# Mounting_PCB_B.net
KiCad netlist of a schematic drawn in Altium Designer
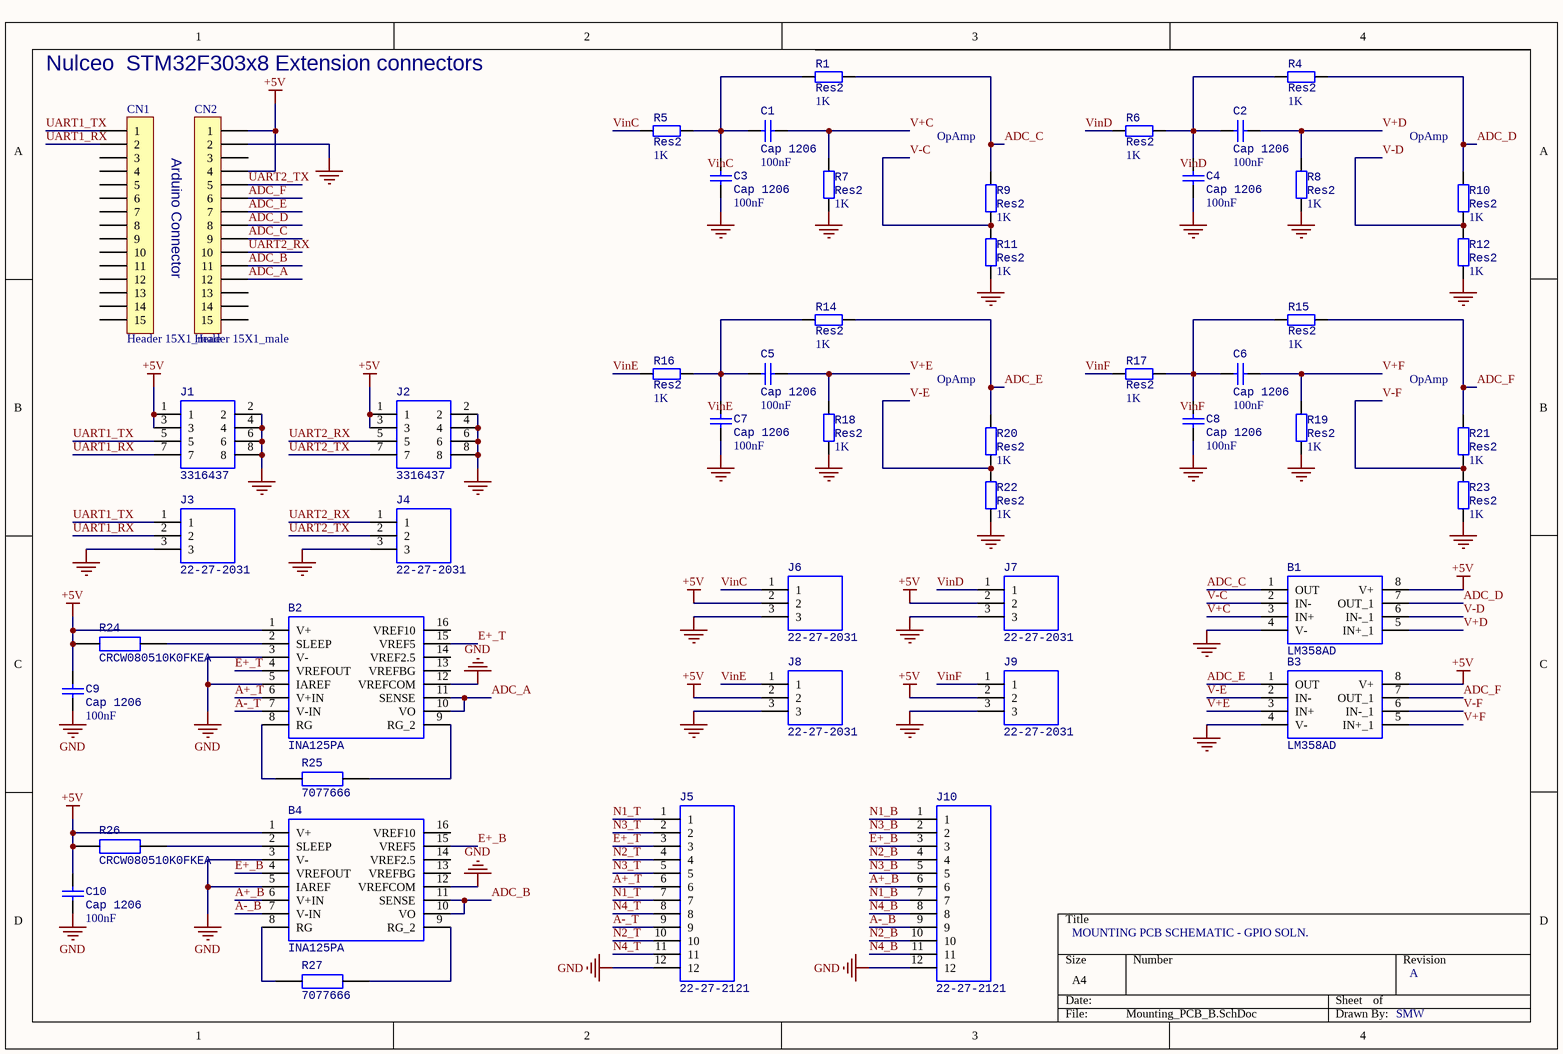
[diagram p0: Mounting_PCB_B.SchDoc]

(export (version "E")
  (design (tool "Eeschema 10.0.6"))
  (components
    (comp (ref "B1")
      (value "LM358AD")
      (footprint "SOIC127P600X175-8N")
      (description "LM358AD, Dual Operational Amplifier 1.1MHz 5 to 28V, 8-Pin SO")
      (fields (field (name "RS PART NUMBER") "1657542"))
      (libsource (lib "LM358AD") (part "LM358AD"))
    )
    (comp (ref "B2")
      (value "INA125PA")
      (footprint "DIP254P762X508-16")
      (description "Instrumentation Amplifier with Precision Voltage Reference")
      (fields (field (name "RS PART NUMBER") "2521593P"))
      (libsource (lib "INA125PA") (part "INA125PA"))
    )
    (comp (ref "B3")
      (value "LM358AD")
      (footprint "SOIC127P600X175-8N")
      (description "LM358AD, Dual Operational Amplifier 1.1MHz 5 to 28V, 8-Pin SO")
      (fields (field (name "RS PART NUMBER") "1657542"))
      (libsource (lib "LM358AD") (part "LM358AD"))
    )
    (comp (ref "B4")
      (value "INA125PA")
      (footprint "DIP254P762X508-16")
      (description "Instrumentation Amplifier with Precision Voltage Reference")
      (fields (field (name "RS PART NUMBER") "2521593P"))
      (libsource (lib "INA125PA") (part "INA125PA"))
    )
    (comp (ref "C1")
      (value "Cap 1206")
      (footprint "C1206")
      (description "Capacitor (Semiconductor SIM Model)")
      (fields (field (name "ALTIUM_VALUE") "100nF") (field (name "PUBLISHER") "Altium Limited"))
      (libsource (lib "Miscellaneous Devices") (part "Cap Semi"))
    )
    (comp (ref "C2")
      (value "Cap 1206")
      (footprint "C1206")
      (description "Capacitor (Semiconductor SIM Model)")
      (fields (field (name "ALTIUM_VALUE") "100nF") (field (name "PUBLISHER") "Altium Limited"))
      (libsource (lib "Miscellaneous Devices") (part "Cap Semi"))
    )
    (comp (ref "C3")
      (value "Cap 1206")
      (footprint "C1206")
      (description "Capacitor (Semiconductor SIM Model)")
      (fields (field (name "ALTIUM_VALUE") "100nF") (field (name "PUBLISHER") "Altium Limited"))
      (libsource (lib "Miscellaneous Devices") (part "Cap Semi"))
    )
    (comp (ref "C4")
      (value "Cap 1206")
      (footprint "C1206")
      (description "Capacitor (Semiconductor SIM Model)")
      (fields (field (name "ALTIUM_VALUE") "100nF") (field (name "PUBLISHER") "Altium Limited"))
      (libsource (lib "Miscellaneous Devices") (part "Cap Semi"))
    )
    (comp (ref "C5")
      (value "Cap 1206")
      (footprint "C1206")
      (description "Capacitor (Semiconductor SIM Model)")
      (fields (field (name "ALTIUM_VALUE") "100nF") (field (name "PUBLISHER") "Altium Limited"))
      (libsource (lib "Miscellaneous Devices") (part "Cap Semi"))
    )
    (comp (ref "C6")
      (value "Cap 1206")
      (footprint "C1206")
      (description "Capacitor (Semiconductor SIM Model)")
      (fields (field (name "ALTIUM_VALUE") "100nF") (field (name "PUBLISHER") "Altium Limited"))
      (libsource (lib "Miscellaneous Devices") (part "Cap Semi"))
    )
    (comp (ref "C7")
      (value "Cap 1206")
      (footprint "C1206")
      (description "Capacitor (Semiconductor SIM Model)")
      (fields (field (name "ALTIUM_VALUE") "100nF") (field (name "PUBLISHER") "Altium Limited"))
      (libsource (lib "Miscellaneous Devices") (part "Cap Semi"))
    )
    (comp (ref "C8")
      (value "Cap 1206")
      (footprint "C1206")
      (description "Capacitor (Semiconductor SIM Model)")
      (fields (field (name "ALTIUM_VALUE") "100nF") (field (name "PUBLISHER") "Altium Limited"))
      (libsource (lib "Miscellaneous Devices") (part "Cap Semi"))
    )
    (comp (ref "C9")
      (value "Cap 1206")
      (footprint "C1206")
      (description "Capacitor (Semiconductor SIM Model)")
      (fields (field (name "ALTIUM_VALUE") "100nF") (field (name "PUBLISHER") "Altium Limited"))
      (libsource (lib "Miscellaneous Devices") (part "Cap Semi"))
    )
    (comp (ref "C10")
      (value "Cap 1206")
      (footprint "C1206")
      (description "Capacitor (Semiconductor SIM Model)")
      (fields (field (name "ALTIUM_VALUE") "100nF") (field (name "PUBLISHER") "Altium Limited"))
      (libsource (lib "Miscellaneous Devices") (part "Cap Semi"))
    )
    (comp (ref "CN1")
      (value "Header 15X1_male")
      (footprint "HDR_1x15_2R54_V_F")
      (description "Header, 10-Pin, Single row,female")
      (fields (field (name "PUBLISHER") "Altium Limited"))
      (libsource (lib "") (part "Header 15X1_Female_1_1"))
    )
    (comp (ref "CN2")
      (value "Header 15X1_male")
      (footprint "HDR_1x15_2R54_V_F")
      (description "Header, 10-Pin, Single row,female")
      (fields (field (name "PUBLISHER") "Altium Limited"))
      (libsource (lib "MB1180") (part "Header 15X1_Female_1"))
    )
    (comp (ref "J1") (value "3316437") (footprint "RJ45-8") (libsource (lib "3316437") (part "3316437")))
    (comp (ref "J2") (value "3316437") (footprint "RJ45-8") (libsource (lib "3316437") (part "3316437")))
    (comp (ref "J3")
      (value "22-27-2031")
      (footprint "SHDR3W64P0X254_1X3_762X580X1170P")
      (fields (field (name "RS PART NUMBER") "1707102"))
      (libsource (lib "22-27-2031") (part "22-27-2031"))
    )
    (comp (ref "J4")
      (value "22-27-2031")
      (footprint "SHDR3W64P0X254_1X3_762X580X1170P")
      (fields (field (name "RS PART NUMBER") "1707102"))
      (libsource (lib "22-27-2031") (part "22-27-2031"))
    )
    (comp (ref "J5")
      (value "22-27-2121")
      (footprint "HDRV12W64P0X254_1X12_3048X580X1170P")
      (fields (field (name "RS PART NUMBER") "1707108"))
      (libsource (lib "22-27-2121") (part "22-27-2121"))
    )
    (comp (ref "J6")
      (value "22-27-2031")
      (footprint "SHDR3W64P0X254_1X3_762X580X1170P")
      (fields (field (name "RS PART NUMBER") "1707102"))
      (libsource (lib "22-27-2031") (part "22-27-2031"))
    )
    (comp (ref "J7")
      (value "22-27-2031")
      (footprint "SHDR3W64P0X254_1X3_762X580X1170P")
      (fields (field (name "RS PART NUMBER") "1707102"))
      (libsource (lib "22-27-2031") (part "22-27-2031"))
    )
    (comp (ref "J8")
      (value "22-27-2031")
      (footprint "SHDR3W64P0X254_1X3_762X580X1170P")
      (fields (field (name "RS PART NUMBER") "1707102"))
      (libsource (lib "22-27-2031") (part "22-27-2031"))
    )
    (comp (ref "J9")
      (value "22-27-2031")
      (footprint "SHDR3W64P0X254_1X3_762X580X1170P")
      (fields (field (name "RS PART NUMBER") "1707102"))
      (libsource (lib "22-27-2031") (part "22-27-2031"))
    )
    (comp (ref "J10")
      (value "22-27-2121")
      (footprint "HDRV12W64P0X254_1X12_3048X580X1170P")
      (fields (field (name "RS PART NUMBER") "1707108"))
      (libsource (lib "22-27-2121") (part "22-27-2121"))
    )
    (comp (ref "R1")
      (value "Res2")
      (footprint "C1206")
      (description "Resistor")
      (fields (field (name "ALTIUM_VALUE") "1K") (field (name "PUBLISHER") "Altium Limited"))
      (libsource (lib "") (part "Res2_1"))
    )
    (comp (ref "R4")
      (value "Res2")
      (footprint "C1206")
      (description "Resistor")
      (fields (field (name "ALTIUM_VALUE") "1K") (field (name "PUBLISHER") "Altium Limited"))
      (libsource (lib "") (part "Res2_1"))
    )
    (comp (ref "R5")
      (value "Res2")
      (footprint "C1206")
      (description "Resistor")
      (fields (field (name "ALTIUM_VALUE") "1K") (field (name "PUBLISHER") "Altium Limited"))
      (libsource (lib "") (part "Res2_1"))
    )
    (comp (ref "R6")
      (value "Res2")
      (footprint "C1206")
      (description "Resistor")
      (fields (field (name "ALTIUM_VALUE") "1K") (field (name "PUBLISHER") "Altium Limited"))
      (libsource (lib "") (part "Res2_1"))
    )
    (comp (ref "R7")
      (value "Res2")
      (footprint "C1206")
      (description "Resistor")
      (fields (field (name "ALTIUM_VALUE") "1K") (field (name "PUBLISHER") "Altium Limited"))
      (libsource (lib "Miscellaneous Devices") (part "Res2"))
    )
    (comp (ref "R8")
      (value "Res2")
      (footprint "C1206")
      (description "Resistor")
      (fields (field (name "ALTIUM_VALUE") "1K") (field (name "PUBLISHER") "Altium Limited"))
      (libsource (lib "Miscellaneous Devices") (part "Res2"))
    )
    (comp (ref "R9")
      (value "Res2")
      (footprint "C1206")
      (description "Resistor")
      (fields (field (name "ALTIUM_VALUE") "1K") (field (name "PUBLISHER") "Altium Limited"))
      (libsource (lib "Miscellaneous Devices") (part "Res2"))
    )
    (comp (ref "R10")
      (value "Res2")
      (footprint "C1206")
      (description "Resistor")
      (fields (field (name "ALTIUM_VALUE") "1K") (field (name "PUBLISHER") "Altium Limited"))
      (libsource (lib "Miscellaneous Devices") (part "Res2"))
    )
    (comp (ref "R11")
      (value "Res2")
      (footprint "C1206")
      (description "Resistor")
      (fields (field (name "ALTIUM_VALUE") "1K") (field (name "PUBLISHER") "Altium Limited"))
      (libsource (lib "Miscellaneous Devices") (part "Res2"))
    )
    (comp (ref "R12")
      (value "Res2")
      (footprint "C1206")
      (description "Resistor")
      (fields (field (name "ALTIUM_VALUE") "1K") (field (name "PUBLISHER") "Altium Limited"))
      (libsource (lib "Miscellaneous Devices") (part "Res2"))
    )
    (comp (ref "R14")
      (value "Res2")
      (footprint "C1206")
      (description "Resistor")
      (fields (field (name "ALTIUM_VALUE") "1K") (field (name "PUBLISHER") "Altium Limited"))
      (libsource (lib "") (part "Res2_1"))
    )
    (comp (ref "R15")
      (value "Res2")
      (footprint "C1206")
      (description "Resistor")
      (fields (field (name "ALTIUM_VALUE") "1K") (field (name "PUBLISHER") "Altium Limited"))
      (libsource (lib "") (part "Res2_1"))
    )
    (comp (ref "R16")
      (value "Res2")
      (footprint "C1206")
      (description "Resistor")
      (fields (field (name "ALTIUM_VALUE") "1K") (field (name "PUBLISHER") "Altium Limited"))
      (libsource (lib "") (part "Res2_1"))
    )
    (comp (ref "R17")
      (value "Res2")
      (footprint "C1206")
      (description "Resistor")
      (fields (field (name "ALTIUM_VALUE") "1K") (field (name "PUBLISHER") "Altium Limited"))
      (libsource (lib "") (part "Res2_1"))
    )
    (comp (ref "R18")
      (value "Res2")
      (footprint "C1206")
      (description "Resistor")
      (fields (field (name "ALTIUM_VALUE") "1K") (field (name "PUBLISHER") "Altium Limited"))
      (libsource (lib "Miscellaneous Devices") (part "Res2"))
    )
    (comp (ref "R19")
      (value "Res2")
      (footprint "C1206")
      (description "Resistor")
      (fields (field (name "ALTIUM_VALUE") "1K") (field (name "PUBLISHER") "Altium Limited"))
      (libsource (lib "Miscellaneous Devices") (part "Res2"))
    )
    (comp (ref "R20")
      (value "Res2")
      (footprint "C1206")
      (description "Resistor")
      (fields (field (name "ALTIUM_VALUE") "1K") (field (name "PUBLISHER") "Altium Limited"))
      (libsource (lib "Miscellaneous Devices") (part "Res2"))
    )
    (comp (ref "R21")
      (value "Res2")
      (footprint "C1206")
      (description "Resistor")
      (fields (field (name "ALTIUM_VALUE") "1K") (field (name "PUBLISHER") "Altium Limited"))
      (libsource (lib "Miscellaneous Devices") (part "Res2"))
    )
    (comp (ref "R22")
      (value "Res2")
      (footprint "C1206")
      (description "Resistor")
      (fields (field (name "ALTIUM_VALUE") "1K") (field (name "PUBLISHER") "Altium Limited"))
      (libsource (lib "Miscellaneous Devices") (part "Res2"))
    )
    (comp (ref "R23")
      (value "Res2")
      (footprint "C1206")
      (description "Resistor")
      (fields (field (name "ALTIUM_VALUE") "1K") (field (name "PUBLISHER") "Altium Limited"))
      (libsource (lib "Miscellaneous Devices") (part "Res2"))
    )
    (comp (ref "R24")
      (value "CRCW080510K0FKEA")
      (footprint "RESC2012X50N")
      (fields (field (name "RS PART NUMBER") "1694499"))
      (libsource (lib "CRCW080510K0FKEA") (part "CRCW080510K0FKEA"))
    )
    (comp (ref "R25")
      (value "7077666")
      (footprint "RESAD1550W58L630D230")
      (description "RS Pro RS Series Axial Carbon Resistor 1k 5% 0.25W -500  +350ppm/C")
      (libsource (lib "7077666") (part "7077666"))
    )
    (comp (ref "R26")
      (value "CRCW080510K0FKEA")
      (footprint "RESC2012X50N")
      (fields (field (name "RS PART NUMBER") "1694499"))
      (libsource (lib "CRCW080510K0FKEA") (part "CRCW080510K0FKEA"))
    )
    (comp (ref "R27")
      (value "7077666")
      (footprint "RESAD1550W58L630D230")
      (description "RS Pro RS Series Axial Carbon Resistor 1k 5% 0.25W -500  +350ppm/C")
      (libsource (lib "7077666") (part "7077666"))
    )
  )
  (nets
    (net (code "1") (name "+5V") (class "Default")
      (node (ref "B1") (pin "8") (pinfunction "V+_8") (pintype "passive"))
      (node (ref "B2") (pin "1") (pinfunction "V+_1") (pintype "passive"))
      (node (ref "B3") (pin "8") (pinfunction "V+_8") (pintype "passive"))
      (node (ref "B4") (pin "1") (pinfunction "V+_1") (pintype "passive"))
      (node (ref "C10") (pin "2") (pinfunction "2_2") (pintype "passive"))
      (node (ref "C9") (pin "2") (pinfunction "2_2") (pintype "passive"))
      (node (ref "CN2") (pin "1") (pinfunction "1_1") (pintype "passive"))
      (node (ref "CN2") (pin "4") (pinfunction "4_4") (pintype "passive"))
      (node (ref "J1") (pin "1") (pinfunction "1_1") (pintype "passive"))
      (node (ref "J1") (pin "3") (pinfunction "3_3") (pintype "passive"))
      (node (ref "J2") (pin "1") (pinfunction "1_1") (pintype "passive"))
      (node (ref "J2") (pin "3") (pinfunction "3_3") (pintype "passive"))
      (node (ref "J6") (pin "2") (pinfunction "2_2") (pintype "passive"))
      (node (ref "J7") (pin "2") (pinfunction "2_2") (pintype "passive"))
      (node (ref "J8") (pin "2") (pinfunction "2_2") (pintype "passive"))
      (node (ref "J9") (pin "2") (pinfunction "2_2") (pintype "passive"))
      (node (ref "R24") (pin "1") (pinfunction "1_1") (pintype "passive"))
      (node (ref "R26") (pin "1") (pinfunction "1_1") (pintype "passive"))
    )
    (net (code "2") (name "/A+_B") (class "Default")
      (node (ref "B4") (pin "6") (pinfunction "V+IN_6") (pintype "passive"))
      (node (ref "J10") (pin "6") (pinfunction "6_6") (pintype "passive"))
    )
    (net (code "3") (name "/A+_T") (class "Default")
      (node (ref "B2") (pin "6") (pinfunction "V+IN_6") (pintype "passive"))
      (node (ref "J5") (pin "6") (pinfunction "6_6") (pintype "passive"))
    )
    (net (code "4") (name "/A-_B") (class "Default")
      (node (ref "B4") (pin "7") (pinfunction "V-IN_7") (pintype "passive"))
      (node (ref "J10") (pin "9") (pinfunction "9_9") (pintype "passive"))
    )
    (net (code "5") (name "/A-_T") (class "Default")
      (node (ref "B2") (pin "7") (pinfunction "V-IN_7") (pintype "passive"))
      (node (ref "J5") (pin "9") (pinfunction "9_9") (pintype "passive"))
    )
    (net (code "6") (name "/ADC_A") (class "Default")
      (node (ref "B2") (pin "10") (pinfunction "VO_10") (pintype "passive"))
      (node (ref "B2") (pin "11") (pinfunction "SENSE_11") (pintype "passive"))
      (node (ref "CN2") (pin "12") (pinfunction "12_12") (pintype "passive"))
    )
    (net (code "7") (name "/ADC_B") (class "Default")
      (node (ref "B4") (pin "10") (pinfunction "VO_10") (pintype "passive"))
      (node (ref "B4") (pin "11") (pinfunction "SENSE_11") (pintype "passive"))
      (node (ref "CN2") (pin "11") (pinfunction "11_11") (pintype "passive"))
    )
    (net (code "8") (name "/ADC_C") (class "Default")
      (node (ref "B1") (pin "1") (pinfunction "OUT_1") (pintype "passive"))
      (node (ref "CN2") (pin "9") (pinfunction "9_9") (pintype "passive"))
      (node (ref "R1") (pin "2") (pinfunction "2_2") (pintype "passive"))
      (node (ref "R9") (pin "2") (pinfunction "2_2") (pintype "passive"))
    )
    (net (code "9") (name "/ADC_D") (class "Default")
      (node (ref "B1") (pin "7") (pinfunction "OUT_1_7") (pintype "passive"))
      (node (ref "CN2") (pin "8") (pinfunction "8_8") (pintype "passive"))
      (node (ref "R10") (pin "2") (pinfunction "2_2") (pintype "passive"))
      (node (ref "R4") (pin "2") (pinfunction "2_2") (pintype "passive"))
    )
    (net (code "10") (name "/ADC_E") (class "Default")
      (node (ref "B3") (pin "1") (pinfunction "OUT_1") (pintype "passive"))
      (node (ref "CN2") (pin "7") (pinfunction "7_7") (pintype "passive"))
      (node (ref "R14") (pin "2") (pinfunction "2_2") (pintype "passive"))
      (node (ref "R20") (pin "2") (pinfunction "2_2") (pintype "passive"))
    )
    (net (code "11") (name "/ADC_F") (class "Default")
      (node (ref "B3") (pin "7") (pinfunction "OUT_1_7") (pintype "passive"))
      (node (ref "CN2") (pin "6") (pinfunction "6_6") (pintype "passive"))
      (node (ref "R15") (pin "2") (pinfunction "2_2") (pintype "passive"))
      (node (ref "R21") (pin "2") (pinfunction "2_2") (pintype "passive"))
    )
    (net (code "12") (name "/E+_B") (class "Default")
      (node (ref "B4") (pin "15") (pinfunction "VREF5_15") (pintype "passive"))
      (node (ref "B4") (pin "4") (pinfunction "VREFOUT_4") (pintype "passive"))
      (node (ref "J10") (pin "3") (pinfunction "3_3") (pintype "passive"))
    )
    (net (code "13") (name "/E+_T") (class "Default")
      (node (ref "B2") (pin "15") (pinfunction "VREF5_15") (pintype "passive"))
      (node (ref "B2") (pin "4") (pinfunction "VREFOUT_4") (pintype "passive"))
      (node (ref "J5") (pin "3") (pinfunction "3_3") (pintype "passive"))
    )
    (net (code "14") (name "/N1_B") (class "Default")
      (node (ref "J10") (pin "1") (pinfunction "1_1") (pintype "passive"))
      (node (ref "J10") (pin "7") (pinfunction "7_7") (pintype "passive"))
    )
    (net (code "15") (name "/N1_T") (class "Default")
      (node (ref "J5") (pin "1") (pinfunction "1_1") (pintype "passive"))
      (node (ref "J5") (pin "7") (pinfunction "7_7") (pintype "passive"))
    )
    (net (code "16") (name "/N2_B") (class "Default")
      (node (ref "J10") (pin "10") (pinfunction "10_10") (pintype "passive"))
      (node (ref "J10") (pin "4") (pinfunction "4_4") (pintype "passive"))
    )
    (net (code "17") (name "/N2_T") (class "Default")
      (node (ref "J5") (pin "10") (pinfunction "10_10") (pintype "passive"))
      (node (ref "J5") (pin "4") (pinfunction "4_4") (pintype "passive"))
    )
    (net (code "18") (name "/N3_B") (class "Default")
      (node (ref "J10") (pin "2") (pinfunction "2_2") (pintype "passive"))
      (node (ref "J10") (pin "5") (pinfunction "5_5") (pintype "passive"))
    )
    (net (code "19") (name "/N3_T") (class "Default")
      (node (ref "J5") (pin "2") (pinfunction "2_2") (pintype "passive"))
      (node (ref "J5") (pin "5") (pinfunction "5_5") (pintype "passive"))
    )
    (net (code "20") (name "/N4_B") (class "Default")
      (node (ref "J10") (pin "11") (pinfunction "11_11") (pintype "passive"))
      (node (ref "J10") (pin "8") (pinfunction "8_8") (pintype "passive"))
    )
    (net (code "21") (name "/N4_T") (class "Default")
      (node (ref "J5") (pin "11") (pinfunction "11_11") (pintype "passive"))
      (node (ref "J5") (pin "8") (pinfunction "8_8") (pintype "passive"))
    )
    (net (code "22") (name "/UART1_RX") (class "Default")
      (node (ref "CN1") (pin "2") (pinfunction "2_2") (pintype "passive"))
      (node (ref "J1") (pin "7") (pinfunction "7_7") (pintype "passive"))
      (node (ref "J3") (pin "2") (pinfunction "2_2") (pintype "passive"))
    )
    (net (code "23") (name "/UART1_TX") (class "Default")
      (node (ref "CN1") (pin "1") (pinfunction "1_1") (pintype "passive"))
      (node (ref "J1") (pin "5") (pinfunction "5_5") (pintype "passive"))
      (node (ref "J3") (pin "1") (pinfunction "1_1") (pintype "passive"))
    )
    (net (code "24") (name "/UART2_RX") (class "Default")
      (node (ref "CN2") (pin "10") (pinfunction "10_10") (pintype "passive"))
      (node (ref "J2") (pin "5") (pinfunction "5_5") (pintype "passive"))
      (node (ref "J4") (pin "1") (pinfunction "1_1") (pintype "passive"))
    )
    (net (code "25") (name "/UART2_TX") (class "Default")
      (node (ref "CN2") (pin "5") (pinfunction "5_5") (pintype "passive"))
      (node (ref "J2") (pin "7") (pinfunction "7_7") (pintype "passive"))
      (node (ref "J4") (pin "2") (pinfunction "2_2") (pintype "passive"))
    )
    (net (code "26") (name "/V+C") (class "Default")
      (node (ref "B1") (pin "3") (pinfunction "IN+_3") (pintype "passive"))
      (node (ref "C1") (pin "1") (pinfunction "1_1") (pintype "passive"))
      (node (ref "R7") (pin "2") (pinfunction "2_2") (pintype "passive"))
    )
    (net (code "27") (name "/V+D") (class "Default")
      (node (ref "B1") (pin "5") (pinfunction "IN+_1_5") (pintype "passive"))
      (node (ref "C2") (pin "1") (pinfunction "1_1") (pintype "passive"))
      (node (ref "R8") (pin "2") (pinfunction "2_2") (pintype "passive"))
    )
    (net (code "28") (name "/V+E") (class "Default")
      (node (ref "B3") (pin "3") (pinfunction "IN+_3") (pintype "passive"))
      (node (ref "C5") (pin "1") (pinfunction "1_1") (pintype "passive"))
      (node (ref "R18") (pin "2") (pinfunction "2_2") (pintype "passive"))
    )
    (net (code "29") (name "/V+F") (class "Default")
      (node (ref "B3") (pin "5") (pinfunction "IN+_1_5") (pintype "passive"))
      (node (ref "C6") (pin "1") (pinfunction "1_1") (pintype "passive"))
      (node (ref "R19") (pin "2") (pinfunction "2_2") (pintype "passive"))
    )
    (net (code "30") (name "/V-C") (class "Default")
      (node (ref "B1") (pin "2") (pinfunction "IN-_2") (pintype "passive"))
      (node (ref "R11") (pin "2") (pinfunction "2_2") (pintype "passive"))
      (node (ref "R9") (pin "1") (pinfunction "1_1") (pintype "passive"))
    )
    (net (code "31") (name "/V-D") (class "Default")
      (node (ref "B1") (pin "6") (pinfunction "IN-_1_6") (pintype "passive"))
      (node (ref "R10") (pin "1") (pinfunction "1_1") (pintype "passive"))
      (node (ref "R12") (pin "2") (pinfunction "2_2") (pintype "passive"))
    )
    (net (code "32") (name "/V-E") (class "Default")
      (node (ref "B3") (pin "2") (pinfunction "IN-_2") (pintype "passive"))
      (node (ref "R20") (pin "1") (pinfunction "1_1") (pintype "passive"))
      (node (ref "R22") (pin "2") (pinfunction "2_2") (pintype "passive"))
    )
    (net (code "33") (name "/V-F") (class "Default")
      (node (ref "B3") (pin "6") (pinfunction "IN-_1_6") (pintype "passive"))
      (node (ref "R21") (pin "1") (pinfunction "1_1") (pintype "passive"))
      (node (ref "R23") (pin "2") (pinfunction "2_2") (pintype "passive"))
    )
    (net (code "34") (name "/VinC") (class "Default")
      (node (ref "J6") (pin "1") (pinfunction "1_1") (pintype "passive"))
      (node (ref "R5") (pin "1") (pinfunction "1_1") (pintype "passive"))
    )
    (net (code "35") (name "/VinD") (class "Default")
      (node (ref "J7") (pin "1") (pinfunction "1_1") (pintype "passive"))
      (node (ref "R6") (pin "1") (pinfunction "1_1") (pintype "passive"))
    )
    (net (code "36") (name "/VinE") (class "Default")
      (node (ref "J8") (pin "1") (pinfunction "1_1") (pintype "passive"))
      (node (ref "R16") (pin "1") (pinfunction "1_1") (pintype "passive"))
    )
    (net (code "37") (name "/VinF") (class "Default")
      (node (ref "J9") (pin "1") (pinfunction "1_1") (pintype "passive"))
      (node (ref "R17") (pin "1") (pinfunction "1_1") (pintype "passive"))
    )
    (net (code "38") (name "GND") (class "Default")
      (node (ref "B1") (pin "4") (pinfunction "V-_4") (pintype "passive"))
      (node (ref "B2") (pin "12") (pinfunction "VREFCOM_12") (pintype "passive"))
      (node (ref "B2") (pin "3") (pinfunction "V-_3") (pintype "passive"))
      (node (ref "B2") (pin "5") (pinfunction "IAREF_5") (pintype "passive"))
      (node (ref "B3") (pin "4") (pinfunction "V-_4") (pintype "passive"))
      (node (ref "B4") (pin "12") (pinfunction "VREFCOM_12") (pintype "passive"))
      (node (ref "B4") (pin "3") (pinfunction "V-_3") (pintype "passive"))
      (node (ref "B4") (pin "5") (pinfunction "IAREF_5") (pintype "passive"))
      (node (ref "C10") (pin "1") (pinfunction "1_1") (pintype "passive"))
      (node (ref "C3") (pin "1") (pinfunction "1_1") (pintype "passive"))
      (node (ref "C4") (pin "1") (pinfunction "1_1") (pintype "passive"))
      (node (ref "C7") (pin "1") (pinfunction "1_1") (pintype "passive"))
      (node (ref "C8") (pin "1") (pinfunction "1_1") (pintype "passive"))
      (node (ref "C9") (pin "1") (pinfunction "1_1") (pintype "passive"))
      (node (ref "CN2") (pin "2") (pinfunction "2_2") (pintype "passive"))
      (node (ref "J1") (pin "2") (pinfunction "2_2") (pintype "passive"))
      (node (ref "J1") (pin "4") (pinfunction "4_4") (pintype "passive"))
      (node (ref "J1") (pin "6") (pinfunction "6_6") (pintype "passive"))
      (node (ref "J1") (pin "8") (pinfunction "8_8") (pintype "passive"))
      (node (ref "J10") (pin "12") (pinfunction "12_12") (pintype "passive"))
      (node (ref "J2") (pin "2") (pinfunction "2_2") (pintype "passive"))
      (node (ref "J2") (pin "4") (pinfunction "4_4") (pintype "passive"))
      (node (ref "J2") (pin "6") (pinfunction "6_6") (pintype "passive"))
      (node (ref "J2") (pin "8") (pinfunction "8_8") (pintype "passive"))
      (node (ref "J3") (pin "3") (pinfunction "3_3") (pintype "passive"))
      (node (ref "J4") (pin "3") (pinfunction "3_3") (pintype "passive"))
      (node (ref "J5") (pin "12") (pinfunction "12_12") (pintype "passive"))
      (node (ref "J6") (pin "3") (pinfunction "3_3") (pintype "passive"))
      (node (ref "J7") (pin "3") (pinfunction "3_3") (pintype "passive"))
      (node (ref "J8") (pin "3") (pinfunction "3_3") (pintype "passive"))
      (node (ref "J9") (pin "3") (pinfunction "3_3") (pintype "passive"))
      (node (ref "R11") (pin "1") (pinfunction "1_1") (pintype "passive"))
      (node (ref "R12") (pin "1") (pinfunction "1_1") (pintype "passive"))
      (node (ref "R18") (pin "1") (pinfunction "1_1") (pintype "passive"))
      (node (ref "R19") (pin "1") (pinfunction "1_1") (pintype "passive"))
      (node (ref "R22") (pin "1") (pinfunction "1_1") (pintype "passive"))
      (node (ref "R23") (pin "1") (pinfunction "1_1") (pintype "passive"))
      (node (ref "R7") (pin "1") (pinfunction "1_1") (pintype "passive"))
      (node (ref "R8") (pin "1") (pinfunction "1_1") (pintype "passive"))
    )
    (net (code "39") (name "Net-(B2-RG)") (class "Default")
      (node (ref "B2") (pin "8") (pinfunction "RG_8") (pintype "passive"))
      (node (ref "R25") (pin "1") (pinfunction "1_1") (pintype "passive"))
    )
    (net (code "40") (name "Net-(B2-RG_2)") (class "Default")
      (node (ref "B2") (pin "9") (pinfunction "RG_2_9") (pintype "passive"))
      (node (ref "R25") (pin "2") (pinfunction "2_2") (pintype "passive"))
    )
    (net (code "41") (name "Net-(B2-SLEEP)") (class "Default")
      (node (ref "B2") (pin "2") (pinfunction "SLEEP_2") (pintype "passive"))
      (node (ref "R24") (pin "2") (pinfunction "2_2") (pintype "passive"))
    )
    (net (code "42") (name "Net-(B4-RG)") (class "Default")
      (node (ref "B4") (pin "8") (pinfunction "RG_8") (pintype "passive"))
      (node (ref "R27") (pin "1") (pinfunction "1_1") (pintype "passive"))
    )
    (net (code "43") (name "Net-(B4-RG_2)") (class "Default")
      (node (ref "B4") (pin "9") (pinfunction "RG_2_9") (pintype "passive"))
      (node (ref "R27") (pin "2") (pinfunction "2_2") (pintype "passive"))
    )
    (net (code "44") (name "Net-(B4-SLEEP)") (class "Default")
      (node (ref "B4") (pin "2") (pinfunction "SLEEP_2") (pintype "passive"))
      (node (ref "R26") (pin "2") (pinfunction "2_2") (pintype "passive"))
    )
    (net (code "45") (name "Net-(C1-Pad2)") (class "Default")
      (node (ref "C1") (pin "2") (pinfunction "2_2") (pintype "passive"))
      (node (ref "C3") (pin "2") (pinfunction "2_2") (pintype "passive"))
      (node (ref "R1") (pin "1") (pinfunction "1_1") (pintype "passive"))
      (node (ref "R5") (pin "2") (pinfunction "2_2") (pintype "passive"))
    )
    (net (code "46") (name "Net-(C2-Pad2)") (class "Default")
      (node (ref "C2") (pin "2") (pinfunction "2_2") (pintype "passive"))
      (node (ref "C4") (pin "2") (pinfunction "2_2") (pintype "passive"))
      (node (ref "R4") (pin "1") (pinfunction "1_1") (pintype "passive"))
      (node (ref "R6") (pin "2") (pinfunction "2_2") (pintype "passive"))
    )
    (net (code "47") (name "Net-(C5-Pad2)") (class "Default")
      (node (ref "C5") (pin "2") (pinfunction "2_2") (pintype "passive"))
      (node (ref "C7") (pin "2") (pinfunction "2_2") (pintype "passive"))
      (node (ref "R14") (pin "1") (pinfunction "1_1") (pintype "passive"))
      (node (ref "R16") (pin "2") (pinfunction "2_2") (pintype "passive"))
    )
    (net (code "48") (name "Net-(C6-Pad2)") (class "Default")
      (node (ref "C6") (pin "2") (pinfunction "2_2") (pintype "passive"))
      (node (ref "C8") (pin "2") (pinfunction "2_2") (pintype "passive"))
      (node (ref "R15") (pin "1") (pinfunction "1_1") (pintype "passive"))
      (node (ref "R17") (pin "2") (pinfunction "2_2") (pintype "passive"))
    )
    (net (code "49") (name "unconnected-(B2-VREF2.5-Pad14)") (class "Default")
      (node (ref "B2") (pin "14") (pinfunction "VREF2.5_14") (pintype "passive"))
    )
    (net (code "50") (name "unconnected-(B2-VREF10-Pad16)") (class "Default")
      (node (ref "B2") (pin "16") (pinfunction "VREF10_16") (pintype "passive"))
    )
    (net (code "51") (name "unconnected-(B2-VREFBG-Pad13)") (class "Default")
      (node (ref "B2") (pin "13") (pinfunction "VREFBG_13") (pintype "passive"))
    )
    (net (code "52") (name "unconnected-(B4-VREF2.5-Pad14)") (class "Default")
      (node (ref "B4") (pin "14") (pinfunction "VREF2.5_14") (pintype "passive"))
    )
    (net (code "53") (name "unconnected-(B4-VREF10-Pad16)") (class "Default")
      (node (ref "B4") (pin "16") (pinfunction "VREF10_16") (pintype "passive"))
    )
    (net (code "54") (name "unconnected-(B4-VREFBG-Pad13)") (class "Default")
      (node (ref "B4") (pin "13") (pinfunction "VREFBG_13") (pintype "passive"))
    )
    (net (code "55") (name "unconnected-(CN1-Pad3)") (class "Default")
      (node (ref "CN1") (pin "3") (pinfunction "3_3") (pintype "passive"))
    )
    (net (code "56") (name "unconnected-(CN1-Pad4)") (class "Default")
      (node (ref "CN1") (pin "4") (pinfunction "4_4") (pintype "passive"))
    )
    (net (code "57") (name "unconnected-(CN1-Pad5)") (class "Default")
      (node (ref "CN1") (pin "5") (pinfunction "5_5") (pintype "passive"))
    )
    (net (code "58") (name "unconnected-(CN1-Pad6)") (class "Default")
      (node (ref "CN1") (pin "6") (pinfunction "6_6") (pintype "passive"))
    )
    (net (code "59") (name "unconnected-(CN1-Pad7)") (class "Default")
      (node (ref "CN1") (pin "7") (pinfunction "7_7") (pintype "passive"))
    )
    (net (code "60") (name "unconnected-(CN1-Pad8)") (class "Default")
      (node (ref "CN1") (pin "8") (pinfunction "8_8") (pintype "passive"))
    )
    (net (code "61") (name "unconnected-(CN1-Pad9)") (class "Default")
      (node (ref "CN1") (pin "9") (pinfunction "9_9") (pintype "passive"))
    )
    (net (code "62") (name "unconnected-(CN1-Pad10)") (class "Default")
      (node (ref "CN1") (pin "10") (pinfunction "10_10") (pintype "passive"))
    )
    (net (code "63") (name "unconnected-(CN1-Pad11)") (class "Default")
      (node (ref "CN1") (pin "11") (pinfunction "11_11") (pintype "passive"))
    )
    (net (code "64") (name "unconnected-(CN1-Pad12)") (class "Default")
      (node (ref "CN1") (pin "12") (pinfunction "12_12") (pintype "passive"))
    )
    (net (code "65") (name "unconnected-(CN1-Pad13)") (class "Default")
      (node (ref "CN1") (pin "13") (pinfunction "13_13") (pintype "passive"))
    )
    (net (code "66") (name "unconnected-(CN1-Pad14)") (class "Default")
      (node (ref "CN1") (pin "14") (pinfunction "14_14") (pintype "passive"))
    )
    (net (code "67") (name "unconnected-(CN1-Pad15)") (class "Default")
      (node (ref "CN1") (pin "15") (pinfunction "15_15") (pintype "passive"))
    )
    (net (code "68") (name "unconnected-(CN2-Pad3)") (class "Default")
      (node (ref "CN2") (pin "3") (pinfunction "3_3") (pintype "passive"))
    )
    (net (code "69") (name "unconnected-(CN2-Pad13)") (class "Default")
      (node (ref "CN2") (pin "13") (pinfunction "13_13") (pintype "passive"))
    )
    (net (code "70") (name "unconnected-(CN2-Pad14)") (class "Default")
      (node (ref "CN2") (pin "14") (pinfunction "14_14") (pintype "passive"))
    )
    (net (code "71") (name "unconnected-(CN2-Pad15)") (class "Default")
      (node (ref "CN2") (pin "15") (pinfunction "15_15") (pintype "passive"))
    )
  )
)
